# FourRouterMy.net
KiCad netlist of a schematic drawn in Altium Designer
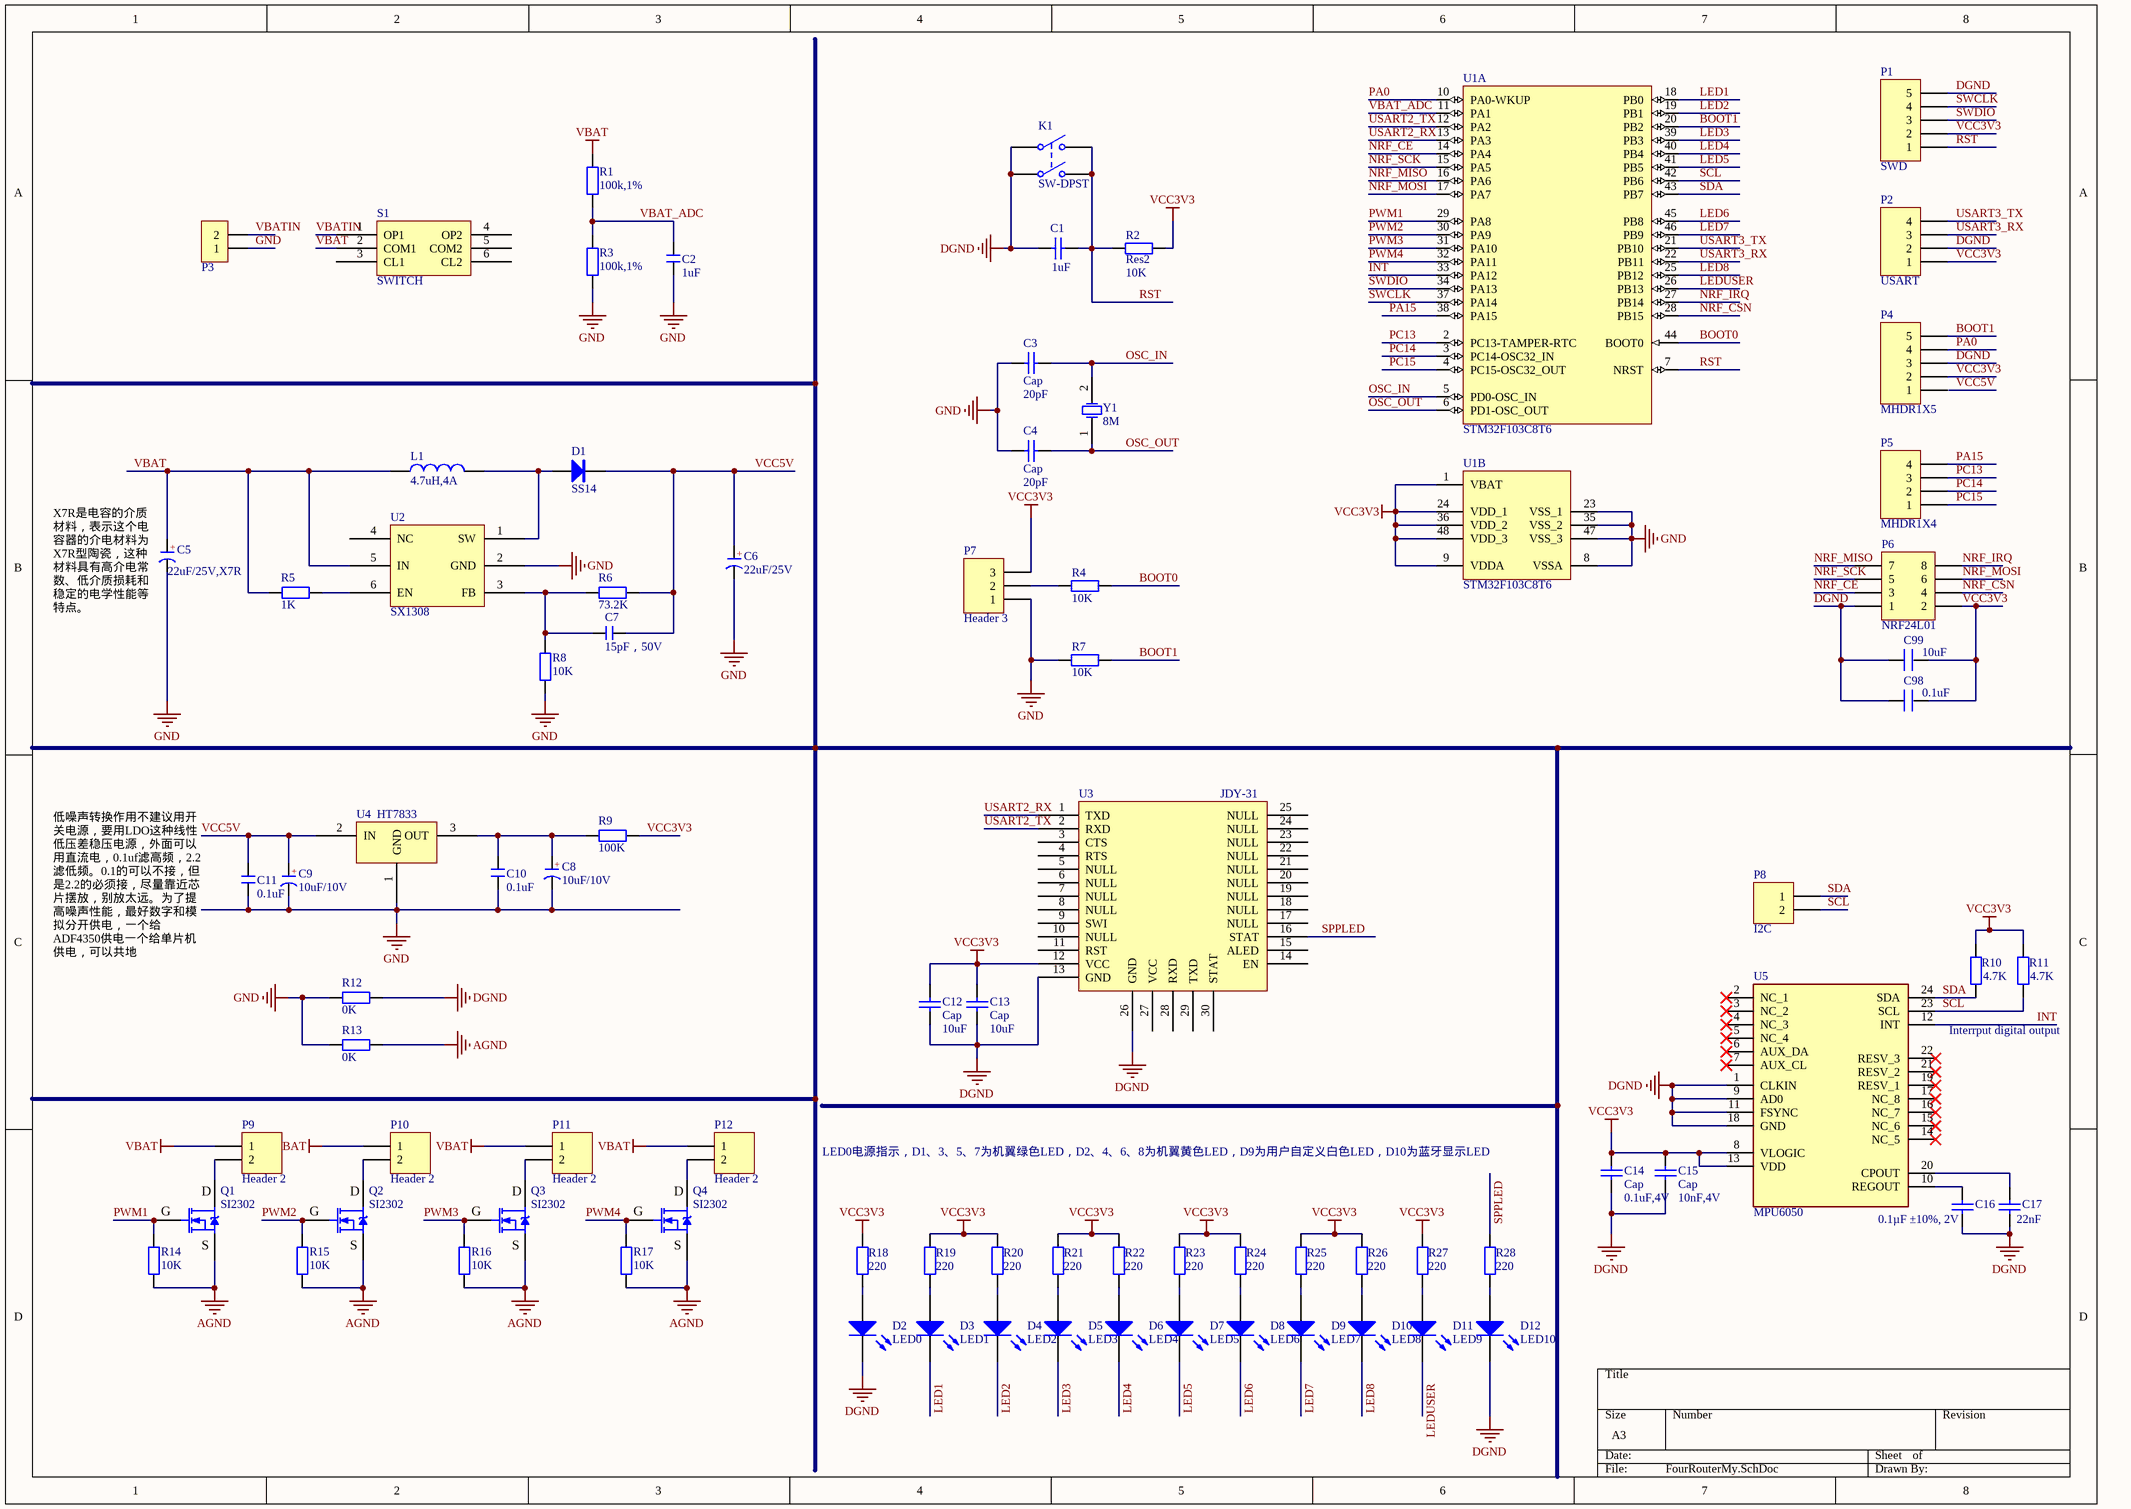
[diagram p0: FourRouterMy.SchDoc]

(export (version "E")
  (design (tool "Eeschema 10.0.6"))
  (components
    (comp (ref "C1")
      (value "1uF")
      (footprint "0603C")
      (description "Capacitor")
      (fields (field (name "Comment") "Cap") (field (name "PUBLISHER") "Altium Limited"))
      (libsource (lib "Miscellaneous Devices") (part "Cap"))
    )
    (comp (ref "C2")
      (value "1uF")
      (footprint "0603C")
      (description "无极性贴片电容")
      (fields (field (name "版权归属") "源创客"))
      (libsource (lib "3.1   - 电阻-电容-电感") (part "C"))
    )
    (comp (ref "C3")
      (value "Cap")
      (footprint "0603C")
      (description "Capacitor")
      (fields (field (name "ALTIUM_VALUE") "20pF") (field (name "PUBLISHER") "Altium Limited"))
      (libsource (lib "Miscellaneous Devices") (part "Cap"))
    )
    (comp (ref "C4")
      (value "Cap")
      (footprint "0603C")
      (description "Capacitor")
      (fields (field (name "ALTIUM_VALUE") "20pF") (field (name "PUBLISHER") "Altium Limited"))
      (libsource (lib "Miscellaneous Devices") (part "Cap"))
    )
    (comp (ref "C5")
      (value "22uF/25V,X7R")
      (footprint "1206C")
      (description "贴片电解电容")
      (fields (field (name "版权归属") "源创客"))
      (libsource (lib "3.1   - 电阻-电容-电感") (part "C-CM"))
    )
    (comp (ref "C6")
      (value "22uF/25V")
      (footprint "1206C")
      (description "贴片电解电容")
      (fields (field (name "版权归属") "源创客"))
      (libsource (lib "3.1   - 电阻-电容-电感") (part "C-CM"))
    )
    (comp (ref "C7")
      (value "15pF，50V")
      (footprint "0603C")
      (description "无极性贴片电容")
      (fields (field (name "版权归属") "源创客"))
      (libsource (lib "3.1   - 电阻-电容-电感") (part "C"))
    )
    (comp (ref "C8")
      (value "10uF/10V")
      (footprint "1206C")
      (description "贴片电解电容")
      (fields (field (name "版权归属") "源创客"))
      (libsource (lib "3.1   - 电阻-电容-电感") (part "C-CM"))
    )
    (comp (ref "C9")
      (value "10uF/10V")
      (footprint "1206C")
      (description "贴片电解电容")
      (fields (field (name "版权归属") "源创客"))
      (libsource (lib "3.1   - 电阻-电容-电感") (part "C-CM"))
    )
    (comp (ref "C10")
      (value "0.1uF")
      (footprint "0603C")
      (description "无极性贴片电容")
      (fields (field (name "版权归属") "源创客"))
      (libsource (lib "3.1   - 电阻-电容-电感") (part "C"))
    )
    (comp (ref "C11")
      (value "0.1uF")
      (footprint "0603C")
      (description "无极性贴片电容")
      (fields (field (name "版权归属") "源创客"))
      (libsource (lib "3.1   - 电阻-电容-电感") (part "C"))
    )
    (comp (ref "C12")
      (value "Cap")
      (footprint "0603C")
      (description "Capacitor")
      (fields (field (name "ALTIUM_VALUE") "10uF") (field (name "PUBLISHER") "Altium Limited"))
      (libsource (lib "Miscellaneous Devices") (part "Cap"))
    )
    (comp (ref "C13")
      (value "Cap")
      (footprint "0603C")
      (description "Capacitor")
      (fields (field (name "ALTIUM_VALUE") "10uF") (field (name "PUBLISHER") "Altium Limited"))
      (libsource (lib "Miscellaneous Devices") (part "Cap"))
    )
    (comp (ref "C14")
      (value "Cap")
      (footprint "0603C")
      (description "Capacitor")
      (fields (field (name "ALTIUM_VALUE") "0.1uF,4V") (field (name "PUBLISHER") "Altium Limited"))
      (libsource (lib "Miscellaneous Devices") (part "Cap"))
    )
    (comp (ref "C15")
      (value "Cap")
      (footprint "0603C")
      (description "Capacitor")
      (fields (field (name "ALTIUM_VALUE") "10nF,4V") (field (name "PUBLISHER") "Altium Limited"))
      (libsource (lib "Miscellaneous Devices") (part "Cap"))
    )
    (comp (ref "C16")
      (value "0.1µF ±10%, 2V")
      (footprint "0603C")
      (description "Capacitor")
      (fields (field (name "Comment") "Cap") (field (name "PUBLISHER") "Altium Limited"))
      (libsource (lib "Miscellaneous Devices") (part "Cap"))
    )
    (comp (ref "C17")
      (value "22nF")
      (footprint "0603C")
      (description "Capacitor")
      (fields (field (name "Comment") "Cap") (field (name "PUBLISHER") "Altium Limited"))
      (libsource (lib "Miscellaneous Devices") (part "Cap"))
    )
    (comp (ref "C98")
      (value "0.1uF")
      (footprint "0603C")
      (fields (field (name "Comment") "1uF"))
      (libsource (lib "Explorer STM32F407封装库") (part "C_1"))
    )
    (comp (ref "C99")
      (value "10uF")
      (footprint "C 0805_L")
      (fields (field (name "Comment") "1uF"))
      (libsource (lib "Explorer STM32F407封装库") (part "C_1"))
    )
    (comp (ref "D1")
      (value "SS14")
      (footprint "SMA")
      (description "肖特基二极管")
      (fields (field (name "版权归属") "源创客"))
      (libsource (lib "8.1   - 二极管-整流桥") (part "SS14"))
    )
    (comp (ref "D2")
      (value "LED0")
      (footprint "LED 0603R")
      (description "Typical INFRARED GaAs LED")
      (fields (field (name "PUBLISHER") "Altium Limited"))
      (libsource (lib "Miscellaneous Devices") (part "LED0"))
    )
    (comp (ref "D3")
      (value "LED1")
      (footprint "LED 0603G")
      (description "Typical INFRARED GaAs LED")
      (fields (field (name "PUBLISHER") "Altium Limited"))
      (libsource (lib "Miscellaneous Devices") (part "LED0"))
    )
    (comp (ref "D4")
      (value "LED2")
      (footprint "LED 0603Y")
      (description "Typical INFRARED GaAs LED")
      (fields (field (name "PUBLISHER") "Altium Limited"))
      (libsource (lib "Miscellaneous Devices") (part "LED0"))
    )
    (comp (ref "D5")
      (value "LED3")
      (footprint "LED 0603G")
      (description "Typical INFRARED GaAs LED")
      (fields (field (name "PUBLISHER") "Altium Limited"))
      (libsource (lib "Miscellaneous Devices") (part "LED0"))
    )
    (comp (ref "D6")
      (value "LED4")
      (footprint "LED 0603Y")
      (description "Typical INFRARED GaAs LED")
      (fields (field (name "PUBLISHER") "Altium Limited"))
      (libsource (lib "Miscellaneous Devices") (part "LED0"))
    )
    (comp (ref "D7")
      (value "LED5")
      (footprint "LED 0603G")
      (description "Typical INFRARED GaAs LED")
      (fields (field (name "PUBLISHER") "Altium Limited"))
      (libsource (lib "Miscellaneous Devices") (part "LED0"))
    )
    (comp (ref "D8")
      (value "LED6")
      (footprint "LED 0603Y")
      (description "Typical INFRARED GaAs LED")
      (fields (field (name "PUBLISHER") "Altium Limited"))
      (libsource (lib "Miscellaneous Devices") (part "LED0"))
    )
    (comp (ref "D9")
      (value "LED7")
      (footprint "LED 0603G")
      (description "Typical INFRARED GaAs LED")
      (fields (field (name "PUBLISHER") "Altium Limited"))
      (libsource (lib "Miscellaneous Devices") (part "LED0"))
    )
    (comp (ref "D10")
      (value "LED8")
      (footprint "LED 0603Y")
      (description "Typical INFRARED GaAs LED")
      (fields (field (name "PUBLISHER") "Altium Limited"))
      (libsource (lib "Miscellaneous Devices") (part "LED0"))
    )
    (comp (ref "D11")
      (value "LED9")
      (footprint "LED 0603W")
      (description "Typical INFRARED GaAs LED")
      (fields (field (name "PUBLISHER") "Altium Limited"))
      (libsource (lib "Miscellaneous Devices") (part "LED0"))
    )
    (comp (ref "D12")
      (value "LED10")
      (footprint "LED 0603B")
      (description "Typical INFRARED GaAs LED")
      (fields (field (name "PUBLISHER") "Altium Limited"))
      (libsource (lib "Miscellaneous Devices") (part "LED0"))
    )
    (comp (ref "K1")
      (value "SW-DPST")
      (footprint "TSW DIP-6*6*6")
      (description "Double-Pole, Single-Throw Switch")
      (fields (field (name "PUBLISHER") "Altium Limited"))
      (libsource (lib "Miscellaneous Devices") (part "SW-DPST"))
    )
    (comp (ref "L1")
      (value "4.7uH,4A")
      (footprint "L 1812")
      (description "小功率贴片电感")
      (fields (field (name "版权归属") "源创客"))
      (libsource (lib "3.1   - 电阻-电容-电感") (part "L"))
    )
    (comp (ref "P1")
      (value "SWD")
      (footprint "XH2.54-WI-5P")
      (description "Header, 5-Pin")
      (fields (field (name "PUBLISHER") "Altium Limited"))
      (libsource (lib "Miscellaneous Connectors") (part "MHDR1X5"))
    )
    (comp (ref "P2")
      (value "USART")
      (footprint "XH2.54-WI-4P")
      (description "Header, 4-Pin")
      (fields (field (name "PUBLISHER") "Altium Limited"))
      (libsource (lib "Miscellaneous Connectors") (part "MHDR1X4"))
    )
    (comp (ref "P3")
      (value "HDR-1X2")
      (footprint "HDR1X2")
      (description "2P接插件")
      (fields (field (name "版权归属") "源创客"))
      (libsource (lib "4.5   - 接插件-脚距2.54") (part "Header 2"))
    )
    (comp (ref "P4")
      (value "MHDR1X5")
      (footprint "HDR2.54-LI-5P")
      (description "Header, 5-Pin")
      (fields (field (name "PUBLISHER") "Altium Limited"))
      (libsource (lib "Miscellaneous Connectors") (part "MHDR1X5"))
    )
    (comp (ref "P5")
      (value "MHDR1X4")
      (footprint "HDR2.54-LI-4P")
      (description "Header, 4-Pin")
      (fields (field (name "PUBLISHER") "Altium Limited"))
      (libsource (lib "Miscellaneous Connectors") (part "MHDR1X4"))
    )
    (comp (ref "P6")
      (value "NRF24L01")
      (footprint "HDR2.54-M-LS-2x4P")
      (description "Header, 4-Pin, Dual row")
      (fields (field (name "PUBLISHER") "Altium Limited"))
      (libsource (lib "Miscellaneous Connectors") (part "MHDR2X4"))
    )
    (comp (ref "P7")
      (value "Header 3")
      (footprint "HDR1X3")
      (description "Header, 3-Pin")
      (fields (field (name "PUBLISHER") "Altium Limited"))
      (libsource (lib "Miscellaneous Connectors") (part "Header 3"))
    )
    (comp (ref "P8")
      (value "I2C")
      (footprint "HDR1X2")
      (description "Header, 2-Pin")
      (fields (field (name "PUBLISHER") "Altium Limited"))
      (libsource (lib "Miscellaneous Connectors") (part "Header 2"))
    )
    (comp (ref "P9")
      (value "Header 2")
      (footprint "HDR1X2")
      (description "Header, 2-Pin")
      (fields (field (name "PUBLISHER") "Altium Limited"))
      (libsource (lib "") (part "Header 2_1"))
    )
    (comp (ref "P10")
      (value "Header 2")
      (footprint "HDR1X2")
      (description "Header, 2-Pin")
      (fields (field (name "PUBLISHER") "Altium Limited"))
      (libsource (lib "") (part "Header 2_1"))
    )
    (comp (ref "P11")
      (value "Header 2")
      (footprint "HDR1X2")
      (description "Header, 2-Pin")
      (fields (field (name "PUBLISHER") "Altium Limited"))
      (libsource (lib "") (part "Header 2_1"))
    )
    (comp (ref "P12")
      (value "Header 2")
      (footprint "HDR1X2")
      (description "Header, 2-Pin")
      (fields (field (name "PUBLISHER") "Altium Limited"))
      (libsource (lib "") (part "Header 2_1"))
    )
    (comp (ref "Q1")
      (value "SI2302")
      (footprint "SOT23-3N")
      (description "N沟道场效应管")
      (fields (field (name "版权归属") "源创客"))
      (libsource (lib "6.1   - 场效应管-可控硅") (part "SI2302"))
    )
    (comp (ref "Q2")
      (value "SI2302")
      (footprint "SOT23-3N")
      (description "N沟道场效应管")
      (fields (field (name "版权归属") "源创客"))
      (libsource (lib "6.1   - 场效应管-可控硅") (part "SI2302"))
    )
    (comp (ref "Q3")
      (value "SI2302")
      (footprint "SOT23-3N")
      (description "N沟道场效应管")
      (fields (field (name "版权归属") "源创客"))
      (libsource (lib "6.1   - 场效应管-可控硅") (part "SI2302"))
    )
    (comp (ref "Q4")
      (value "SI2302")
      (footprint "SOT23-3N")
      (description "N沟道场效应管")
      (fields (field (name "版权归属") "源创客"))
      (libsource (lib "6.1   - 场效应管-可控硅") (part "SI2302"))
    )
    (comp (ref "R1")
      (value "100k,1%")
      (footprint "0603R")
      (description "贴片电阻")
      (fields (field (name "版权归属") "源创客"))
      (libsource (lib "3.1   - 电阻-电容-电感") (part "R"))
    )
    (comp (ref "R2")
      (value "Res2")
      (footprint "0603R")
      (description "Resistor")
      (fields (field (name "ALTIUM_VALUE") "10K") (field (name "PUBLISHER") "Altium Limited"))
      (libsource (lib "") (part "Res2_1"))
    )
    (comp (ref "R3")
      (value "100k,1%")
      (footprint "0603R")
      (description "贴片电阻")
      (fields (field (name "版权归属") "源创客"))
      (libsource (lib "3.1   - 电阻-电容-电感") (part "R"))
    )
    (comp (ref "R4")
      (value "10K")
      (footprint "0603R")
      (description "Resistor")
      (fields (field (name "Comment") "Res2") (field (name "PUBLISHER") "Altium Limited"))
      (libsource (lib "") (part "Res2_1"))
    )
    (comp (ref "R5")
      (value "1K")
      (footprint "0603R")
      (description "贴片电阻")
      (fields (field (name "版权归属") "源创客"))
      (libsource (lib "3.1   - 电阻-电容-电感") (part "R"))
    )
    (comp (ref "R6")
      (value "73.2K")
      (footprint "0603R")
      (description "贴片电阻")
      (fields (field (name "版权归属") "源创客"))
      (libsource (lib "3.1   - 电阻-电容-电感") (part "R"))
    )
    (comp (ref "R7")
      (value "10K")
      (footprint "0603R")
      (description "Resistor")
      (fields (field (name "Comment") "Res2") (field (name "PUBLISHER") "Altium Limited"))
      (libsource (lib "") (part "Res2_1"))
    )
    (comp (ref "R8")
      (value "10K")
      (footprint "0603R")
      (description "贴片电阻")
      (fields (field (name "版权归属") "源创客"))
      (libsource (lib "3.1   - 电阻-电容-电感") (part "R"))
    )
    (comp (ref "R9")
      (value "100K")
      (footprint "0603R")
      (description "贴片电阻")
      (fields (field (name "版权归属") "源创客"))
      (libsource (lib "3.1   - 电阻-电容-电感") (part "R"))
    )
    (comp (ref "R10")
      (value "4.7K")
      (footprint "0603R")
      (description "Resistor")
      (fields (field (name "Comment") "Res2") (field (name "PUBLISHER") "Altium Limited"))
      (libsource (lib "Miscellaneous Devices") (part "Res2"))
    )
    (comp (ref "R11")
      (value "4.7K")
      (footprint "0603R")
      (description "Resistor")
      (fields (field (name "Comment") "Res2") (field (name "PUBLISHER") "Altium Limited"))
      (libsource (lib "Miscellaneous Devices") (part "Res2"))
    )
    (comp (ref "R12")
      (value "0K")
      (footprint "0603R")
      (description "贴片电阻")
      (fields (field (name "版权归属") "源创客"))
      (libsource (lib "3.1   - 电阻-电容-电感") (part "R"))
    )
    (comp (ref "R13")
      (value "0K")
      (footprint "0603R")
      (description "贴片电阻")
      (fields (field (name "版权归属") "源创客"))
      (libsource (lib "3.1   - 电阻-电容-电感") (part "R"))
    )
    (comp (ref "R14")
      (value "10K")
      (footprint "0603R")
      (description "贴片电阻")
      (fields (field (name "版权归属") "源创客"))
      (libsource (lib "3.1   - 电阻-电容-电感") (part "R"))
    )
    (comp (ref "R15")
      (value "10K")
      (footprint "0603R")
      (description "贴片电阻")
      (fields (field (name "版权归属") "源创客"))
      (libsource (lib "3.1   - 电阻-电容-电感") (part "R"))
    )
    (comp (ref "R16")
      (value "10K")
      (footprint "0603R")
      (description "贴片电阻")
      (fields (field (name "版权归属") "源创客"))
      (libsource (lib "3.1   - 电阻-电容-电感") (part "R"))
    )
    (comp (ref "R17")
      (value "10K")
      (footprint "0603R")
      (description "贴片电阻")
      (fields (field (name "版权归属") "源创客"))
      (libsource (lib "3.1   - 电阻-电容-电感") (part "R"))
    )
    (comp (ref "R18")
      (value "220")
      (footprint "0603R")
      (description "Resistor")
      (fields (field (name "Comment") "2") (field (name "PUBLISHER") "Altium Limited"))
      (libsource (lib "Miscellaneous Devices") (part "Res2"))
    )
    (comp (ref "R19")
      (value "220")
      (footprint "0603R")
      (description "Resistor")
      (fields (field (name "Comment") "Res2") (field (name "PUBLISHER") "Altium Limited"))
      (libsource (lib "Miscellaneous Devices") (part "Res2"))
    )
    (comp (ref "R20")
      (value "220")
      (footprint "0603R")
      (description "Resistor")
      (fields (field (name "Comment") "Res2") (field (name "PUBLISHER") "Altium Limited"))
      (libsource (lib "Miscellaneous Devices") (part "Res2"))
    )
    (comp (ref "R21")
      (value "220")
      (footprint "0603R")
      (description "Resistor")
      (fields (field (name "Comment") "Res2") (field (name "PUBLISHER") "Altium Limited"))
      (libsource (lib "Miscellaneous Devices") (part "Res2"))
    )
    (comp (ref "R22")
      (value "220")
      (footprint "0603R")
      (description "Resistor")
      (fields (field (name "Comment") "Res2") (field (name "PUBLISHER") "Altium Limited"))
      (libsource (lib "Miscellaneous Devices") (part "Res2"))
    )
    (comp (ref "R23")
      (value "220")
      (footprint "0603R")
      (description "Resistor")
      (fields (field (name "Comment") "Res2") (field (name "PUBLISHER") "Altium Limited"))
      (libsource (lib "Miscellaneous Devices") (part "Res2"))
    )
    (comp (ref "R24")
      (value "220")
      (footprint "0603R")
      (description "Resistor")
      (fields (field (name "Comment") "Res2") (field (name "PUBLISHER") "Altium Limited"))
      (libsource (lib "Miscellaneous Devices") (part "Res2"))
    )
    (comp (ref "R25")
      (value "220")
      (footprint "0603R")
      (description "Resistor")
      (fields (field (name "Comment") "Res2") (field (name "PUBLISHER") "Altium Limited"))
      (libsource (lib "Miscellaneous Devices") (part "Res2"))
    )
    (comp (ref "R26")
      (value "220")
      (footprint "0603R")
      (description "Resistor")
      (fields (field (name "Comment") "Res2") (field (name "PUBLISHER") "Altium Limited"))
      (libsource (lib "Miscellaneous Devices") (part "Res2"))
    )
    (comp (ref "R27")
      (value "220")
      (footprint "0603R")
      (description "Resistor")
      (fields (field (name "Comment") "Res2") (field (name "PUBLISHER") "Altium Limited"))
      (libsource (lib "Miscellaneous Devices") (part "Res2"))
    )
    (comp (ref "R28")
      (value "220")
      (footprint "0603R")
      (description "Resistor")
      (fields (field (name "Comment") "Res2") (field (name "PUBLISHER") "Altium Limited"))
      (libsource (lib "Miscellaneous Devices") (part "Res2"))
    )
    (comp (ref "S1") (value "SWITCH") (footprint "SS-12F23") (libsource (lib "FourRouterMy") (part "SWITCH")))
    (comp (ref "U1")
      (value "STM32F103C8T6")
      (footprint "LQFP-48_M")
      (libsource (lib "STMicroelectronics STM32 F1") (part "STM32F103C8T6"))
    )
    (comp (ref "U2") (value "SX1308") (footprint "SOT23-6") (libsource (lib "FourRouterMy") (part "SX1308")))
    (comp (ref "U3")
      (value "JDY-31")
      (footprint "JDY-31-SMD")
      (libsource (lib "FourRouterMy") (part "SPP-C"))
    )
    (comp (ref "U4") (value "HT7833") (footprint "SOT-89") (libsource (lib "FourRouterMy") (part "HT7833")))
    (comp (ref "U5")
      (value "MPU6050")
      (footprint "MPU6050")
      (description "Accelerometer and Gyroscope Digital Output 2.5V/3.3V 24-Pin QFN EP")
      (libsource (lib "FourRouterMy") (part "MPU6050"))
    )
    (comp (ref "Y1")
      (value "8M")
      (footprint "OSC HC-49S")
      (description "Crystal Oscillator")
      (fields (field (name "PUBLISHER") "Altium Limited"))
      (libsource (lib "Miscellaneous Devices") (part "XTAL"))
    )
  )
  (nets
    (net (code "2") (name "/BOOT0") (class "Default")
      (node (ref "R4") (pin "2") (pinfunction "2_2") (pintype "passive"))
      (node (ref "U1") (pin "44") (pinfunction "BOOT0_44") (pintype "input"))
    )
    (net (code "3") (name "/BOOT1") (class "Default")
      (node (ref "P4") (pin "5") (pinfunction "5_5") (pintype "passive"))
      (node (ref "R7") (pin "2") (pinfunction "2_2") (pintype "passive"))
      (node (ref "U1") (pin "20") (pinfunction "PB2_20") (pintype "bidirectional"))
    )
    (net (code "4") (name "/INT") (class "Default")
      (node (ref "U1") (pin "33") (pinfunction "PA12_33") (pintype "bidirectional"))
      (node (ref "U5") (pin "12") (pinfunction "INT_12") (pintype "passive"))
    )
    (net (code "5") (name "/LED1") (class "Default")
      (node (ref "D3") (pin "2") (pinfunction "K_2") (pintype "passive"))
      (node (ref "U1") (pin "18") (pinfunction "PB0_18") (pintype "bidirectional"))
    )
    (net (code "6") (name "/LED2") (class "Default")
      (node (ref "D4") (pin "2") (pinfunction "K_2") (pintype "passive"))
      (node (ref "U1") (pin "19") (pinfunction "PB1_19") (pintype "bidirectional"))
    )
    (net (code "7") (name "/LED3") (class "Default")
      (node (ref "D5") (pin "2") (pinfunction "K_2") (pintype "passive"))
      (node (ref "U1") (pin "39") (pinfunction "PB3_39") (pintype "bidirectional"))
    )
    (net (code "8") (name "/LED4") (class "Default")
      (node (ref "D6") (pin "2") (pinfunction "K_2") (pintype "passive"))
      (node (ref "U1") (pin "40") (pinfunction "PB4_40") (pintype "bidirectional"))
    )
    (net (code "9") (name "/LED5") (class "Default")
      (node (ref "D7") (pin "2") (pinfunction "K_2") (pintype "passive"))
      (node (ref "U1") (pin "41") (pinfunction "PB5_41") (pintype "bidirectional"))
    )
    (net (code "10") (name "/LED6") (class "Default")
      (node (ref "D8") (pin "2") (pinfunction "K_2") (pintype "passive"))
      (node (ref "U1") (pin "45") (pinfunction "PB8_45") (pintype "bidirectional"))
    )
    (net (code "11") (name "/LED7") (class "Default")
      (node (ref "D9") (pin "2") (pinfunction "K_2") (pintype "passive"))
      (node (ref "U1") (pin "46") (pinfunction "PB9_46") (pintype "bidirectional"))
    )
    (net (code "12") (name "/LED8") (class "Default")
      (node (ref "D10") (pin "2") (pinfunction "K_2") (pintype "passive"))
      (node (ref "U1") (pin "25") (pinfunction "PB12_25") (pintype "bidirectional"))
    )
    (net (code "13") (name "/LEDUSER") (class "Default")
      (node (ref "D11") (pin "2") (pinfunction "K_2") (pintype "passive"))
      (node (ref "U1") (pin "26") (pinfunction "PB13_26") (pintype "bidirectional"))
    )
    (net (code "14") (name "/NRF_CE") (class "Default")
      (node (ref "P6") (pin "3") (pinfunction "3_3") (pintype "passive"))
      (node (ref "U1") (pin "14") (pinfunction "PA4_14") (pintype "bidirectional"))
    )
    (net (code "15") (name "/NRF_CSN") (class "Default")
      (node (ref "P6") (pin "4") (pinfunction "4_4") (pintype "passive"))
      (node (ref "U1") (pin "28") (pinfunction "PB15_28") (pintype "bidirectional"))
    )
    (net (code "16") (name "/NRF_IRQ") (class "Default")
      (node (ref "P6") (pin "8") (pinfunction "8_8") (pintype "passive"))
      (node (ref "U1") (pin "27") (pinfunction "PB14_27") (pintype "bidirectional"))
    )
    (net (code "17") (name "/NRF_MISO") (class "Default")
      (node (ref "P6") (pin "7") (pinfunction "7_7") (pintype "passive"))
      (node (ref "U1") (pin "16") (pinfunction "PA6_16") (pintype "bidirectional"))
    )
    (net (code "18") (name "/NRF_MOSI") (class "Default")
      (node (ref "P6") (pin "6") (pinfunction "6_6") (pintype "passive"))
      (node (ref "U1") (pin "17") (pinfunction "PA7_17") (pintype "bidirectional"))
    )
    (net (code "19") (name "/NRF_SCK") (class "Default")
      (node (ref "P6") (pin "5") (pinfunction "5_5") (pintype "passive"))
      (node (ref "U1") (pin "15") (pinfunction "PA5_15") (pintype "bidirectional"))
    )
    (net (code "20") (name "/OSC_IN") (class "Default")
      (node (ref "C3") (pin "2") (pinfunction "2_2") (pintype "passive"))
      (node (ref "U1") (pin "5") (pinfunction "PD0-OSC_IN_5") (pintype "bidirectional"))
      (node (ref "Y1") (pin "2") (pinfunction "OSC2_2") (pintype "passive"))
    )
    (net (code "21") (name "/OSC_OUT") (class "Default")
      (node (ref "C4") (pin "2") (pinfunction "2_2") (pintype "passive"))
      (node (ref "U1") (pin "6") (pinfunction "PD1-OSC_OUT_6") (pintype "bidirectional"))
      (node (ref "Y1") (pin "1") (pinfunction "OSC1_1") (pintype "passive"))
    )
    (net (code "22") (name "/PA0") (class "Default")
      (node (ref "P4") (pin "4") (pinfunction "4_4") (pintype "passive"))
      (node (ref "U1") (pin "10") (pinfunction "PA0-WKUP_10") (pintype "bidirectional"))
    )
    (net (code "23") (name "/PA15") (class "Default")
      (node (ref "P5") (pin "4") (pinfunction "4_4") (pintype "passive"))
      (node (ref "U1") (pin "38") (pinfunction "PA15_38") (pintype "bidirectional"))
    )
    (net (code "24") (name "/PC13") (class "Default")
      (node (ref "P5") (pin "3") (pinfunction "3_3") (pintype "passive"))
      (node (ref "U1") (pin "2") (pinfunction "PC13-TAMPER-RTC_2") (pintype "bidirectional"))
    )
    (net (code "25") (name "/PC14") (class "Default")
      (node (ref "P5") (pin "2") (pinfunction "2_2") (pintype "passive"))
      (node (ref "U1") (pin "3") (pinfunction "PC14-OSC32_IN_3") (pintype "bidirectional"))
    )
    (net (code "26") (name "/PC15") (class "Default")
      (node (ref "P5") (pin "1") (pinfunction "1_1") (pintype "passive"))
      (node (ref "U1") (pin "4") (pinfunction "PC15-OSC32_OUT_4") (pintype "bidirectional"))
    )
    (net (code "27") (name "/PWM1") (class "Default")
      (node (ref "Q1") (pin "1") (pinfunction "G_1") (pintype "passive"))
      (node (ref "R14") (pin "2") (pinfunction "2_2") (pintype "passive"))
      (node (ref "U1") (pin "29") (pinfunction "PA8_29") (pintype "bidirectional"))
    )
    (net (code "28") (name "/PWM2") (class "Default")
      (node (ref "Q2") (pin "1") (pinfunction "G_1") (pintype "passive"))
      (node (ref "R15") (pin "2") (pinfunction "2_2") (pintype "passive"))
      (node (ref "U1") (pin "30") (pinfunction "PA9_30") (pintype "bidirectional"))
    )
    (net (code "29") (name "/PWM3") (class "Default")
      (node (ref "Q3") (pin "1") (pinfunction "G_1") (pintype "passive"))
      (node (ref "R16") (pin "2") (pinfunction "2_2") (pintype "passive"))
      (node (ref "U1") (pin "31") (pinfunction "PA10_31") (pintype "bidirectional"))
    )
    (net (code "30") (name "/PWM4") (class "Default")
      (node (ref "Q4") (pin "1") (pinfunction "G_1") (pintype "passive"))
      (node (ref "R17") (pin "2") (pinfunction "2_2") (pintype "passive"))
      (node (ref "U1") (pin "32") (pinfunction "PA11_32") (pintype "bidirectional"))
    )
    (net (code "31") (name "/RST") (class "Default")
      (node (ref "C1") (pin "2") (pinfunction "2_2") (pintype "passive"))
      (node (ref "K1") (pin "2") (pinfunction "NO1_2") (pintype "passive"))
      (node (ref "K1") (pin "4") (pinfunction "NO2_4") (pintype "passive"))
      (node (ref "P1") (pin "1") (pinfunction "1_1") (pintype "passive"))
      (node (ref "R2") (pin "1") (pinfunction "1_1") (pintype "passive"))
      (node (ref "U1") (pin "7") (pinfunction "NRST_7") (pintype "bidirectional"))
    )
    (net (code "32") (name "/SCL") (class "Default")
      (node (ref "P8") (pin "2") (pinfunction "2_2") (pintype "passive"))
      (node (ref "R11") (pin "1") (pinfunction "1_1") (pintype "passive"))
      (node (ref "U1") (pin "42") (pinfunction "PB6_42") (pintype "bidirectional"))
      (node (ref "U5") (pin "23") (pinfunction "SCL_23") (pintype "passive"))
    )
    (net (code "33") (name "/SDA") (class "Default")
      (node (ref "P8") (pin "1") (pinfunction "1_1") (pintype "passive"))
      (node (ref "R10") (pin "1") (pinfunction "1_1") (pintype "passive"))
      (node (ref "U1") (pin "43") (pinfunction "PB7_43") (pintype "bidirectional"))
      (node (ref "U5") (pin "24") (pinfunction "SDA_24") (pintype "passive"))
    )
    (net (code "34") (name "/SPPLED") (class "Default")
      (node (ref "R28") (pin "2") (pinfunction "2_2") (pintype "passive"))
      (node (ref "U3") (pin "16") (pinfunction "STAT_16") (pintype "passive"))
    )
    (net (code "35") (name "/SWCLK") (class "Default")
      (node (ref "P1") (pin "4") (pinfunction "4_4") (pintype "passive"))
      (node (ref "U1") (pin "37") (pinfunction "PA14_37") (pintype "bidirectional"))
    )
    (net (code "36") (name "/SWDIO") (class "Default")
      (node (ref "P1") (pin "3") (pinfunction "3_3") (pintype "passive"))
      (node (ref "U1") (pin "34") (pinfunction "PA13_34") (pintype "bidirectional"))
    )
    (net (code "37") (name "/USART2_RX") (class "Default")
      (node (ref "U1") (pin "13") (pinfunction "PA3_13") (pintype "bidirectional"))
      (node (ref "U3") (pin "1") (pinfunction "TXD_1") (pintype "passive"))
    )
    (net (code "38") (name "/USART2_TX") (class "Default")
      (node (ref "U1") (pin "12") (pinfunction "PA2_12") (pintype "bidirectional"))
      (node (ref "U3") (pin "2") (pinfunction "RXD_2") (pintype "passive"))
    )
    (net (code "39") (name "/USART3_RX") (class "Default")
      (node (ref "P2") (pin "3") (pinfunction "3_3") (pintype "passive"))
      (node (ref "U1") (pin "22") (pinfunction "PB11_22") (pintype "bidirectional"))
    )
    (net (code "40") (name "/USART3_TX") (class "Default")
      (node (ref "P2") (pin "4") (pinfunction "4_4") (pintype "passive"))
      (node (ref "U1") (pin "21") (pinfunction "PB10_21") (pintype "bidirectional"))
    )
    (net (code "41") (name "/VBATIN") (class "Default")
      (node (ref "P3") (pin "2") (pinfunction "2_2") (pintype "passive"))
      (node (ref "S1") (pin "1") (pinfunction "OP1_1") (pintype "passive"))
    )
    (net (code "42") (name "/VBAT_ADC") (class "Default")
      (node (ref "C2") (pin "1") (pinfunction "1_1") (pintype "passive"))
      (node (ref "R1") (pin "1") (pinfunction "1_1") (pintype "passive"))
      (node (ref "R3") (pin "2") (pinfunction "2_2") (pintype "passive"))
      (node (ref "U1") (pin "11") (pinfunction "PA1_11") (pintype "bidirectional"))
    )
    (net (code "43") (name "/VCC5V") (class "Default")
      (node (ref "C11") (pin "2") (pinfunction "2_2") (pintype "passive"))
      (node (ref "C6") (pin "1") (pinfunction "A_1") (pintype "passive"))
      (node (ref "C7") (pin "2") (pinfunction "2_2") (pintype "passive"))
      (node (ref "C9") (pin "1") (pinfunction "A_1") (pintype "passive"))
      (node (ref "D1") (pin "2") (pinfunction "K_2") (pintype "passive"))
      (node (ref "R6") (pin "2") (pinfunction "2_2") (pintype "passive"))
      (node (ref "U4") (pin "2") (pinfunction "IN_2") (pintype "passive"))
    )
    (net (code "44") (name "AGND") (class "Default")
      (node (ref "Q1") (pin "2") (pinfunction "S_2") (pintype "passive"))
      (node (ref "Q2") (pin "2") (pinfunction "S_2") (pintype "passive"))
      (node (ref "Q3") (pin "2") (pinfunction "S_2") (pintype "passive"))
      (node (ref "Q4") (pin "2") (pinfunction "S_2") (pintype "passive"))
      (node (ref "R13") (pin "2") (pinfunction "2_2") (pintype "passive"))
      (node (ref "R14") (pin "1") (pinfunction "1_1") (pintype "passive"))
      (node (ref "R15") (pin "1") (pinfunction "1_1") (pintype "passive"))
      (node (ref "R16") (pin "1") (pinfunction "1_1") (pintype "passive"))
      (node (ref "R17") (pin "1") (pinfunction "1_1") (pintype "passive"))
    )
    (net (code "45") (name "DGND") (class "Default")
      (node (ref "C1") (pin "1") (pinfunction "1_1") (pintype "passive"))
      (node (ref "C12") (pin "1") (pinfunction "1_1") (pintype "passive"))
      (node (ref "C13") (pin "1") (pinfunction "1_1") (pintype "passive"))
      (node (ref "C14") (pin "1") (pinfunction "1_1") (pintype "passive"))
      (node (ref "C15") (pin "1") (pinfunction "1_1") (pintype "passive"))
      (node (ref "C16") (pin "1") (pinfunction "1_1") (pintype "passive"))
      (node (ref "C17") (pin "1") (pinfunction "1_1") (pintype "passive"))
      (node (ref "C98") (pin "1") (pintype "passive"))
      (node (ref "C99") (pin "1") (pintype "passive"))
      (node (ref "D12") (pin "2") (pinfunction "K_2") (pintype "passive"))
      (node (ref "D2") (pin "2") (pinfunction "K_2") (pintype "passive"))
      (node (ref "K1") (pin "1") (pinfunction "COMMON1_1") (pintype "passive"))
      (node (ref "K1") (pin "3") (pinfunction "COMMON2_3") (pintype "passive"))
      (node (ref "P1") (pin "5") (pinfunction "5_5") (pintype "passive"))
      (node (ref "P2") (pin "2") (pinfunction "2_2") (pintype "passive"))
      (node (ref "P4") (pin "3") (pinfunction "3_3") (pintype "passive"))
      (node (ref "P6") (pin "1") (pinfunction "1_1") (pintype "passive"))
      (node (ref "R12") (pin "2") (pinfunction "2_2") (pintype "passive"))
      (node (ref "U3") (pin "13") (pinfunction "GND_13") (pintype "passive"))
      (node (ref "U3") (pin "26") (pinfunction "GND_26") (pintype "passive"))
      (node (ref "U5") (pin "1") (pinfunction "CLKIN_1") (pintype "passive"))
      (node (ref "U5") (pin "11") (pinfunction "FSYNC_11") (pintype "passive"))
      (node (ref "U5") (pin "18") (pinfunction "GND_18") (pintype "passive"))
      (node (ref "U5") (pin "9") (pinfunction "AD0_9") (pintype "passive"))
    )
    (net (code "46") (name "GND") (class "Default")
      (node (ref "C10") (pin "1") (pinfunction "1_1") (pintype "passive"))
      (node (ref "C11") (pin "1") (pinfunction "1_1") (pintype "passive"))
      (node (ref "C2") (pin "2") (pinfunction "2_2") (pintype "passive"))
      (node (ref "C3") (pin "1") (pinfunction "1_1") (pintype "passive"))
      (node (ref "C4") (pin "1") (pinfunction "1_1") (pintype "passive"))
      (node (ref "C5") (pin "2") (pinfunction "K_2") (pintype "passive"))
      (node (ref "C6") (pin "2") (pinfunction "K_2") (pintype "passive"))
      (node (ref "C8") (pin "2") (pinfunction "K_2") (pintype "passive"))
      (node (ref "C9") (pin "2") (pinfunction "K_2") (pintype "passive"))
      (node (ref "P3") (pin "1") (pinfunction "1_1") (pintype "passive"))
      (node (ref "P7") (pin "1") (pinfunction "1_1") (pintype "passive"))
      (node (ref "R12") (pin "1") (pinfunction "1_1") (pintype "passive"))
      (node (ref "R13") (pin "1") (pinfunction "1_1") (pintype "passive"))
      (node (ref "R3") (pin "1") (pinfunction "1_1") (pintype "passive"))
      (node (ref "R7") (pin "1") (pinfunction "1_1") (pintype "passive"))
      (node (ref "R8") (pin "1") (pinfunction "1_1") (pintype "passive"))
      (node (ref "U1") (pin "23") (pinfunction "VSS_1_23") (pintype "power_in"))
      (node (ref "U1") (pin "35") (pinfunction "VSS_2_35") (pintype "power_in"))
      (node (ref "U1") (pin "47") (pinfunction "VSS_3_47") (pintype "power_in"))
      (node (ref "U1") (pin "8") (pinfunction "VSSA_8") (pintype "power_in"))
      (node (ref "U2") (pin "2") (pinfunction "GND_2") (pintype "passive"))
      (node (ref "U4") (pin "1") (pinfunction "GND_1") (pintype "passive"))
    )
    (net (code "47") (name "Net-(C8-A)") (class "Default")
      (node (ref "C10") (pin "2") (pinfunction "2_2") (pintype "passive"))
      (node (ref "C8") (pin "1") (pinfunction "A_1") (pintype "passive"))
      (node (ref "R9") (pin "2") (pinfunction "2_2") (pintype "passive"))
      (node (ref "U4") (pin "3") (pinfunction "OUT_3") (pintype "passive"))
    )
    (net (code "48") (name "Net-(D1-A)") (class "Default")
      (node (ref "D1") (pin "1") (pinfunction "A_1") (pintype "passive"))
      (node (ref "L1") (pin "2") (pinfunction "2_2") (pintype "passive"))
      (node (ref "U2") (pin "1") (pinfunction "SW_1") (pintype "passive"))
    )
    (net (code "49") (name "Net-(D2-A)") (class "Default")
      (node (ref "D2") (pin "1") (pinfunction "A_1") (pintype "passive"))
      (node (ref "R18") (pin "1") (pinfunction "1_1") (pintype "passive"))
    )
    (net (code "50") (name "Net-(D3-A)") (class "Default")
      (node (ref "D3") (pin "1") (pinfunction "A_1") (pintype "passive"))
      (node (ref "R19") (pin "1") (pinfunction "1_1") (pintype "passive"))
    )
    (net (code "51") (name "Net-(D4-A)") (class "Default")
      (node (ref "D4") (pin "1") (pinfunction "A_1") (pintype "passive"))
      (node (ref "R20") (pin "1") (pinfunction "1_1") (pintype "passive"))
    )
    (net (code "52") (name "Net-(D5-A)") (class "Default")
      (node (ref "D5") (pin "1") (pinfunction "A_1") (pintype "passive"))
      (node (ref "R21") (pin "1") (pinfunction "1_1") (pintype "passive"))
    )
    (net (code "53") (name "Net-(D6-A)") (class "Default")
      (node (ref "D6") (pin "1") (pinfunction "A_1") (pintype "passive"))
      (node (ref "R22") (pin "1") (pinfunction "1_1") (pintype "passive"))
    )
    (net (code "54") (name "Net-(D7-A)") (class "Default")
      (node (ref "D7") (pin "1") (pinfunction "A_1") (pintype "passive"))
      (node (ref "R23") (pin "1") (pinfunction "1_1") (pintype "passive"))
    )
    (net (code "55") (name "Net-(D8-A)") (class "Default")
      (node (ref "D8") (pin "1") (pinfunction "A_1") (pintype "passive"))
      (node (ref "R24") (pin "1") (pinfunction "1_1") (pintype "passive"))
    )
    (net (code "56") (name "Net-(D9-A)") (class "Default")
      (node (ref "D9") (pin "1") (pinfunction "A_1") (pintype "passive"))
      (node (ref "R25") (pin "1") (pinfunction "1_1") (pintype "passive"))
    )
    (net (code "57") (name "Net-(D10-A)") (class "Default")
      (node (ref "D10") (pin "1") (pinfunction "A_1") (pintype "passive"))
      (node (ref "R26") (pin "1") (pinfunction "1_1") (pintype "passive"))
    )
    (net (code "58") (name "Net-(D11-A)") (class "Default")
      (node (ref "D11") (pin "1") (pinfunction "A_1") (pintype "passive"))
      (node (ref "R27") (pin "1") (pinfunction "1_1") (pintype "passive"))
    )
    (net (code "59") (name "Net-(D12-A)") (class "Default")
      (node (ref "D12") (pin "1") (pinfunction "A_1") (pintype "passive"))
      (node (ref "R28") (pin "1") (pinfunction "1_1") (pintype "passive"))
    )
    (net (code "60") (name "Net-(P7-Pad2)") (class "Default")
      (node (ref "P7") (pin "2") (pinfunction "2_2") (pintype "passive"))
      (node (ref "R4") (pin "1") (pinfunction "1_1") (pintype "passive"))
    )
    (net (code "61") (name "Net-(Q1-D)") (class "Default")
      (node (ref "P9") (pin "2") (pinfunction "2_2") (pintype "passive"))
      (node (ref "Q1") (pin "3") (pinfunction "D_3") (pintype "passive"))
    )
    (net (code "62") (name "Net-(Q2-D)") (class "Default")
      (node (ref "P10") (pin "2") (pinfunction "2_2") (pintype "passive"))
      (node (ref "Q2") (pin "3") (pinfunction "D_3") (pintype "passive"))
    )
    (net (code "63") (name "Net-(Q3-D)") (class "Default")
      (node (ref "P11") (pin "2") (pinfunction "2_2") (pintype "passive"))
      (node (ref "Q3") (pin "3") (pinfunction "D_3") (pintype "passive"))
    )
    (net (code "64") (name "Net-(Q4-D)") (class "Default")
      (node (ref "P12") (pin "2") (pinfunction "2_2") (pintype "passive"))
      (node (ref "Q4") (pin "3") (pinfunction "D_3") (pintype "passive"))
    )
    (net (code "65") (name "Net-(U2-EN)") (class "Default")
      (node (ref "R5") (pin "2") (pinfunction "2_2") (pintype "passive"))
      (node (ref "U2") (pin "6") (pinfunction "EN_6") (pintype "passive"))
    )
    (net (code "66") (name "Net-(U2-FB)") (class "Default")
      (node (ref "C7") (pin "1") (pinfunction "1_1") (pintype "passive"))
      (node (ref "R6") (pin "1") (pinfunction "1_1") (pintype "passive"))
      (node (ref "R8") (pin "2") (pinfunction "2_2") (pintype "passive"))
      (node (ref "U2") (pin "3") (pinfunction "FB_3") (pintype "passive"))
    )
    (net (code "67") (name "Net-(U5-CPOUT)") (class "Default")
      (node (ref "C17") (pin "2") (pinfunction "2_2") (pintype "passive"))
      (node (ref "U5") (pin "20") (pinfunction "CPOUT_20") (pintype "passive"))
    )
    (net (code "68") (name "Net-(U5-REGOUT)") (class "Default")
      (node (ref "C16") (pin "2") (pinfunction "2_2") (pintype "passive"))
      (node (ref "U5") (pin "10") (pinfunction "REGOUT_10") (pintype "passive"))
    )
    (net (code "69") (name "VBAT") (class "Default")
      (node (ref "C5") (pin "1") (pinfunction "A_1") (pintype "passive"))
      (node (ref "L1") (pin "1") (pinfunction "1_1") (pintype "passive"))
      (node (ref "P10") (pin "1") (pinfunction "1_1") (pintype "passive"))
      (node (ref "P11") (pin "1") (pinfunction "1_1") (pintype "passive"))
      (node (ref "P12") (pin "1") (pinfunction "1_1") (pintype "passive"))
      (node (ref "P9") (pin "1") (pinfunction "1_1") (pintype "passive"))
      (node (ref "R1") (pin "2") (pinfunction "2_2") (pintype "passive"))
      (node (ref "R5") (pin "1") (pinfunction "1_1") (pintype "passive"))
      (node (ref "S1") (pin "2") (pinfunction "COM1_2") (pintype "passive"))
      (node (ref "U2") (pin "5") (pinfunction "IN_5") (pintype "passive"))
    )
    (net (code "70") (name "VCC3V3") (class "Default")
      (node (ref "C12") (pin "2") (pinfunction "2_2") (pintype "passive"))
      (node (ref "C13") (pin "2") (pinfunction "2_2") (pintype "passive"))
      (node (ref "C14") (pin "2") (pinfunction "2_2") (pintype "passive"))
      (node (ref "C15") (pin "2") (pinfunction "2_2") (pintype "passive"))
      (node (ref "C98") (pin "2") (pintype "passive"))
      (node (ref "C99") (pin "2") (pintype "passive"))
      (node (ref "P1") (pin "2") (pinfunction "2_2") (pintype "passive"))
      (node (ref "P2") (pin "1") (pinfunction "1_1") (pintype "passive"))
      (node (ref "P4") (pin "2") (pinfunction "2_2") (pintype "passive"))
      (node (ref "P6") (pin "2") (pinfunction "2_2") (pintype "passive"))
      (node (ref "P7") (pin "3") (pinfunction "3_3") (pintype "passive"))
      (node (ref "R10") (pin "2") (pinfunction "2_2") (pintype "passive"))
      (node (ref "R11") (pin "2") (pinfunction "2_2") (pintype "passive"))
      (node (ref "R18") (pin "2") (pinfunction "2_2") (pintype "passive"))
      (node (ref "R19") (pin "2") (pinfunction "2_2") (pintype "passive"))
      (node (ref "R2") (pin "2") (pinfunction "2_2") (pintype "passive"))
      (node (ref "R20") (pin "2") (pinfunction "2_2") (pintype "passive"))
      (node (ref "R21") (pin "2") (pinfunction "2_2") (pintype "passive"))
      (node (ref "R22") (pin "2") (pinfunction "2_2") (pintype "passive"))
      (node (ref "R23") (pin "2") (pinfunction "2_2") (pintype "passive"))
      (node (ref "R24") (pin "2") (pinfunction "2_2") (pintype "passive"))
      (node (ref "R25") (pin "2") (pinfunction "2_2") (pintype "passive"))
      (node (ref "R26") (pin "2") (pinfunction "2_2") (pintype "passive"))
      (node (ref "R27") (pin "2") (pinfunction "2_2") (pintype "passive"))
      (node (ref "R9") (pin "1") (pinfunction "1_1") (pintype "passive"))
      (node (ref "U1") (pin "1") (pinfunction "VBAT_1") (pintype "power_in"))
      (node (ref "U1") (pin "24") (pinfunction "VDD_1_24") (pintype "power_in"))
      (node (ref "U1") (pin "36") (pinfunction "VDD_2_36") (pintype "power_in"))
      (node (ref "U1") (pin "48") (pinfunction "VDD_3_48") (pintype "power_in"))
      (node (ref "U1") (pin "9") (pinfunction "VDDA_9") (pintype "power_in"))
      (node (ref "U3") (pin "12") (pinfunction "VCC_12") (pintype "passive"))
      (node (ref "U5") (pin "13") (pinfunction "VDD_13") (pintype "passive"))
      (node (ref "U5") (pin "8") (pinfunction "VLOGIC_8") (pintype "passive"))
    )
    (net (code "71") (name "unconnected-(P4-Pad1)") (class "Default")
      (node (ref "P4") (pin "1") (pinfunction "1_1") (pintype "passive"))
    )
    (net (code "72") (name "unconnected-(S1-CL1-Pad3)") (class "Default")
      (node (ref "S1") (pin "3") (pinfunction "CL1_3") (pintype "passive"))
    )
    (net (code "73") (name "unconnected-(S1-CL2-Pad6)") (class "Default")
      (node (ref "S1") (pin "6") (pinfunction "CL2_6") (pintype "passive"))
    )
    (net (code "74") (name "unconnected-(S1-COM2-Pad5)") (class "Default")
      (node (ref "S1") (pin "5") (pinfunction "COM2_5") (pintype "passive"))
    )
    (net (code "75") (name "unconnected-(S1-OP2-Pad4)") (class "Default")
      (node (ref "S1") (pin "4") (pinfunction "OP2_4") (pintype "passive"))
    )
    (net (code "76") (name "unconnected-(U2-NC-Pad4)") (class "Default")
      (node (ref "U2") (pin "4") (pinfunction "NC_4") (pintype "passive"))
    )
    (net (code "77") (name "unconnected-(U3-ALED-Pad15)") (class "Default")
      (node (ref "U3") (pin "15") (pinfunction "ALED_15") (pintype "passive"))
    )
    (net (code "78") (name "unconnected-(U3-CTS-Pad3)") (class "Default")
      (node (ref "U3") (pin "3") (pinfunction "CTS_3") (pintype "passive"))
    )
    (net (code "79") (name "unconnected-(U3-EN-Pad14)") (class "Default")
      (node (ref "U3") (pin "14") (pinfunction "EN_14") (pintype "passive"))
    )
    (net (code "80") (name "unconnected-(U3-NULL-Pad5)") (class "Default")
      (node (ref "U3") (pin "5") (pinfunction "NULL_5") (pintype "passive"))
    )
    (net (code "81") (name "unconnected-(U3-NULL-Pad6)") (class "Default")
      (node (ref "U3") (pin "6") (pinfunction "NULL_6") (pintype "passive"))
    )
    (net (code "82") (name "unconnected-(U3-NULL-Pad7)") (class "Default")
      (node (ref "U3") (pin "7") (pinfunction "NULL_7") (pintype "passive"))
    )
    (net (code "83") (name "unconnected-(U3-NULL-Pad8)") (class "Default")
      (node (ref "U3") (pin "8") (pinfunction "NULL_8") (pintype "passive"))
    )
    (net (code "84") (name "unconnected-(U3-NULL-Pad10)") (class "Default")
      (node (ref "U3") (pin "10") (pinfunction "NULL_10") (pintype "passive"))
    )
    (net (code "85") (name "unconnected-(U3-NULL-Pad17)") (class "Default")
      (node (ref "U3") (pin "17") (pinfunction "NULL_17") (pintype "passive"))
    )
    (net (code "86") (name "unconnected-(U3-NULL-Pad18)") (class "Default")
      (node (ref "U3") (pin "18") (pinfunction "NULL_18") (pintype "passive"))
    )
    (net (code "87") (name "unconnected-(U3-NULL-Pad19)") (class "Default")
      (node (ref "U3") (pin "19") (pinfunction "NULL_19") (pintype "passive"))
    )
    (net (code "88") (name "unconnected-(U3-NULL-Pad20)") (class "Default")
      (node (ref "U3") (pin "20") (pinfunction "NULL_20") (pintype "passive"))
    )
    (net (code "89") (name "unconnected-(U3-NULL-Pad21)") (class "Default")
      (node (ref "U3") (pin "21") (pinfunction "NULL_21") (pintype "passive"))
    )
    (net (code "90") (name "unconnected-(U3-NULL-Pad22)") (class "Default")
      (node (ref "U3") (pin "22") (pinfunction "NULL_22") (pintype "passive"))
    )
    (net (code "91") (name "unconnected-(U3-NULL-Pad23)") (class "Default")
      (node (ref "U3") (pin "23") (pinfunction "NULL_23") (pintype "passive"))
    )
    (net (code "92") (name "unconnected-(U3-NULL-Pad24)") (class "Default")
      (node (ref "U3") (pin "24") (pinfunction "NULL_24") (pintype "passive"))
    )
    (net (code "93") (name "unconnected-(U3-NULL-Pad25)") (class "Default")
      (node (ref "U3") (pin "25") (pinfunction "NULL_25") (pintype "passive"))
    )
    (net (code "94") (name "unconnected-(U3-RST-Pad11)") (class "Default")
      (node (ref "U3") (pin "11") (pinfunction "RST_11") (pintype "passive"))
    )
    (net (code "95") (name "unconnected-(U3-RTS-Pad4)") (class "Default")
      (node (ref "U3") (pin "4") (pinfunction "RTS_4") (pintype "passive"))
    )
    (net (code "96") (name "unconnected-(U3-RXD-Pad28)") (class "Default")
      (node (ref "U3") (pin "28") (pinfunction "RXD_28") (pintype "passive"))
    )
    (net (code "97") (name "unconnected-(U3-STAT-Pad30)") (class "Default")
      (node (ref "U3") (pin "30") (pinfunction "STAT_30") (pintype "passive"))
    )
    (net (code "98") (name "unconnected-(U3-SWI-Pad9)") (class "Default")
      (node (ref "U3") (pin "9") (pinfunction "SWI_9") (pintype "passive"))
    )
    (net (code "99") (name "unconnected-(U3-TXD-Pad29)") (class "Default")
      (node (ref "U3") (pin "29") (pinfunction "TXD_29") (pintype "passive"))
    )
    (net (code "100") (name "unconnected-(U3-VCC-Pad27)") (class "Default")
      (node (ref "U3") (pin "27") (pinfunction "VCC_27") (pintype "passive"))
    )
    (net (code "101") (name "unconnected-(U5-AUX_CL-Pad7)") (class "Default")
      (node (ref "U5") (pin "7") (pinfunction "AUX_CL_7") (pintype "passive+no_connect"))
    )
    (net (code "102") (name "unconnected-(U5-AUX_DA-Pad6)") (class "Default")
      (node (ref "U5") (pin "6") (pinfunction "AUX_DA_6") (pintype "passive+no_connect"))
    )
    (net (code "103") (name "unconnected-(U5-NC_1-Pad2)") (class "Default")
      (node (ref "U5") (pin "2") (pinfunction "NC_1_2") (pintype "passive+no_connect"))
    )
    (net (code "104") (name "unconnected-(U5-NC_2-Pad3)") (class "Default")
      (node (ref "U5") (pin "3") (pinfunction "NC_2_3") (pintype "passive+no_connect"))
    )
    (net (code "105") (name "unconnected-(U5-NC_3-Pad4)") (class "Default")
      (node (ref "U5") (pin "4") (pinfunction "NC_3_4") (pintype "passive+no_connect"))
    )
    (net (code "106") (name "unconnected-(U5-NC_4-Pad5)") (class "Default")
      (node (ref "U5") (pin "5") (pinfunction "NC_4_5") (pintype "passive+no_connect"))
    )
    (net (code "107") (name "unconnected-(U5-NC_5-Pad14)") (class "Default")
      (node (ref "U5") (pin "14") (pinfunction "NC_5_14") (pintype "passive+no_connect"))
    )
    (net (code "108") (name "unconnected-(U5-NC_6-Pad15)") (class "Default")
      (node (ref "U5") (pin "15") (pinfunction "NC_6_15") (pintype "passive+no_connect"))
    )
    (net (code "109") (name "unconnected-(U5-NC_7-Pad16)") (class "Default")
      (node (ref "U5") (pin "16") (pinfunction "NC_7_16") (pintype "passive+no_connect"))
    )
    (net (code "110") (name "unconnected-(U5-NC_8-Pad17)") (class "Default")
      (node (ref "U5") (pin "17") (pinfunction "NC_8_17") (pintype "passive+no_connect"))
    )
    (net (code "111") (name "unconnected-(U5-RESV_1-Pad19)") (class "Default")
      (node (ref "U5") (pin "19") (pinfunction "RESV_1_19") (pintype "passive+no_connect"))
    )
    (net (code "112") (name "unconnected-(U5-RESV_2-Pad21)") (class "Default")
      (node (ref "U5") (pin "21") (pinfunction "RESV_2_21") (pintype "passive+no_connect"))
    )
    (net (code "113") (name "unconnected-(U5-RESV_3-Pad22)") (class "Default")
      (node (ref "U5") (pin "22") (pinfunction "RESV_3_22") (pintype "passive+no_connect"))
    )
  )
)
